# Switch.net
KiCad netlist of a schematic drawn in Altium Designer
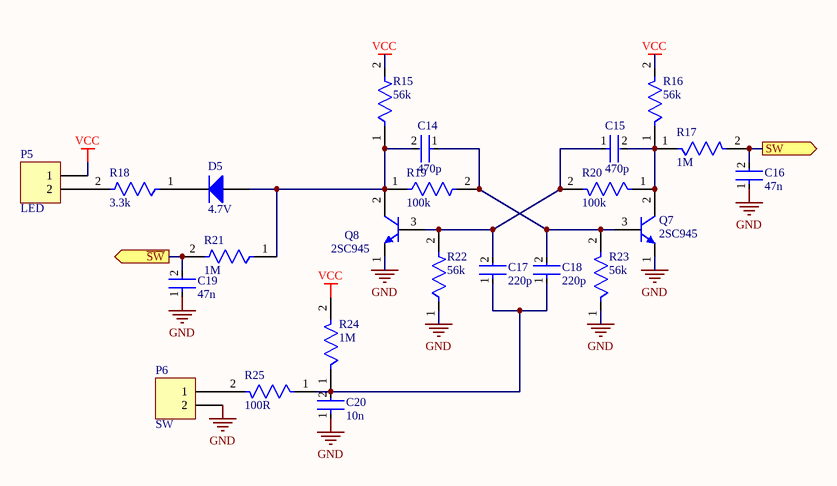
[diagram p0: Switch.SchDoc]

(export (version "E")
  (design (tool "Eeschema 10.0.6"))
  (components
    (comp (ref "C14")
      (value "470p")
      (footprint "FP-CL10-IPC_A")
      (description "Cap Ceramic 1nF 50V C0G ±5% Pad SMD 0603 +125°C T/R")
      (fields (field (name "VOLTAGE") "50V") (field (name "TOLERANCE") "5%"))
      (libsource (lib "Altium Content Vault") (part "b4654b650e69147ec39a6b967a45e02"))
    )
    (comp (ref "C15")
      (value "470p")
      (footprint "FP-CL10-IPC_A")
      (description "Cap Ceramic 1nF 50V C0G ±5% Pad SMD 0603 +125°C T/R")
      (fields (field (name "VOLTAGE") "50V") (field (name "TOLERANCE") "5%"))
      (libsource (lib "Altium Content Vault") (part "b4654b650e69147ec39a6b967a45e02"))
    )
    (comp (ref "C16")
      (value "47n")
      (footprint "FP-CL10-IPC_A")
      (description "Cap Ceramic 1nF 50V C0G ±5% Pad SMD 0603 +125°C T/R")
      (fields (field (name "VOLTAGE") "50V") (field (name "TOLERANCE") "5%"))
      (libsource (lib "Altium Content Vault") (part "b4654b650e69147ec39a6b967a45e02"))
    )
    (comp (ref "C17")
      (value "220p")
      (footprint "FP-CL10-IPC_A")
      (description "Cap Ceramic 1nF 50V C0G ±5% Pad SMD 0603 +125°C T/R")
      (fields (field (name "VOLTAGE") "50V") (field (name "TOLERANCE") "5%"))
      (libsource (lib "Altium Content Vault") (part "b4654b650e69147ec39a6b967a45e02"))
    )
    (comp (ref "C18")
      (value "220p")
      (footprint "FP-CL10-IPC_A")
      (description "Cap Ceramic 1nF 50V C0G ±5% Pad SMD 0603 +125°C T/R")
      (fields (field (name "VOLTAGE") "50V") (field (name "TOLERANCE") "5%"))
      (libsource (lib "Altium Content Vault") (part "b4654b650e69147ec39a6b967a45e02"))
    )
    (comp (ref "C19")
      (value "47n")
      (footprint "FP-CL10-IPC_A")
      (description "Cap Ceramic 1nF 50V C0G ±5% Pad SMD 0603 +125°C T/R")
      (fields (field (name "VOLTAGE") "50V") (field (name "TOLERANCE") "5%"))
      (libsource (lib "Altium Content Vault") (part "b4654b650e69147ec39a6b967a45e02"))
    )
    (comp (ref "C20")
      (value "10n")
      (footprint "FP-CL10-IPC_A")
      (description "Cap Ceramic 1nF 50V C0G ±5% Pad SMD 0603 +125°C T/R")
      (fields (field (name "VOLTAGE") "50V") (field (name "TOLERANCE") "5%"))
      (libsource (lib "Altium Content Vault") (part "b4654b650e69147ec39a6b967a45e02"))
    )
    (comp (ref "D5") (value "4.7V") (footprint "DO-41") (libsource (lib "TH_Symbols") (part "DIODE_SW")))
    (comp (ref "P5")
      (value "LED")
      (footprint "HDR1X2")
      (description "Header, 2-Pin")
      (fields (field (name "PUBLISHER") "Altium Limited"))
      (libsource (lib "Miscellaneous Connectors") (part "Header 2"))
    )
    (comp (ref "P6")
      (value "SW")
      (footprint "HDR1X2")
      (description "Header, 2-Pin")
      (fields (field (name "PUBLISHER") "Altium Limited"))
      (libsource (lib "Miscellaneous Connectors") (part "Header 2"))
    )
    (comp (ref "Q7") (value "2SC945") (footprint "TO-92") (libsource (lib "TH_Symbols") (part "BJT_NPN")))
    (comp (ref "Q8") (value "2SC945") (footprint "TO-92") (libsource (lib "TH_Symbols") (part "BJT_NPN")))
    (comp (ref "R15")
      (value "56k")
      (footprint "FP-RT0805-MFG")
      (description "RES SMD 10K OHM 0.1% 1/8W 0805")
      (fields
        (field (name "MANUFACTURER PART NUMBER") "RT0805BRE0710KL")
        (field (name "MANUFACTURER") "Yageo")
      )
      (libsource (lib "Altium Content Vault") (part "1029c3af85768c4190bb7ad29bc67b5"))
    )
    (comp (ref "R16")
      (value "56k")
      (footprint "FP-RT0805-MFG")
      (description "RES SMD 10K OHM 0.1% 1/8W 0805")
      (fields
        (field (name "MANUFACTURER PART NUMBER") "RT0805BRE0710KL")
        (field (name "MANUFACTURER") "Yageo")
      )
      (libsource (lib "Altium Content Vault") (part "1029c3af85768c4190bb7ad29bc67b5"))
    )
    (comp (ref "R17")
      (value "1M")
      (footprint "FP-RT0805-MFG")
      (description "RES SMD 10K OHM 0.1% 1/8W 0805")
      (fields
        (field (name "MANUFACTURER PART NUMBER") "RT0805BRE0710KL")
        (field (name "MANUFACTURER") "Yageo")
      )
      (libsource (lib "Altium Content Vault") (part "1029c3af85768c4190bb7ad29bc67b5"))
    )
    (comp (ref "R18")
      (value "3.3k")
      (footprint "FP-RT0805-MFG")
      (description "RES SMD 10K OHM 0.1% 1/8W 0805")
      (fields
        (field (name "MANUFACTURER PART NUMBER") "RT0805BRE0710KL")
        (field (name "MANUFACTURER") "Yageo")
      )
      (libsource (lib "Altium Content Vault") (part "1029c3af85768c4190bb7ad29bc67b5"))
    )
    (comp (ref "R19")
      (value "100k")
      (footprint "FP-RT0805-MFG")
      (description "RES SMD 10K OHM 0.1% 1/8W 0805")
      (fields
        (field (name "MANUFACTURER PART NUMBER") "RT0805BRE0710KL")
        (field (name "MANUFACTURER") "Yageo")
      )
      (libsource (lib "Altium Content Vault") (part "1029c3af85768c4190bb7ad29bc67b5"))
    )
    (comp (ref "R20")
      (value "100k")
      (footprint "FP-RT0805-MFG")
      (description "RES SMD 10K OHM 0.1% 1/8W 0805")
      (fields
        (field (name "MANUFACTURER PART NUMBER") "RT0805BRE0710KL")
        (field (name "MANUFACTURER") "Yageo")
      )
      (libsource (lib "Altium Content Vault") (part "1029c3af85768c4190bb7ad29bc67b5"))
    )
    (comp (ref "R21")
      (value "1M")
      (footprint "FP-RT0805-MFG")
      (description "RES SMD 10K OHM 0.1% 1/8W 0805")
      (fields
        (field (name "MANUFACTURER PART NUMBER") "RT0805BRE0710KL")
        (field (name "MANUFACTURER") "Yageo")
      )
      (libsource (lib "Altium Content Vault") (part "1029c3af85768c4190bb7ad29bc67b5"))
    )
    (comp (ref "R22")
      (value "56k")
      (footprint "FP-RT0805-MFG")
      (description "RES SMD 10K OHM 0.1% 1/8W 0805")
      (fields
        (field (name "MANUFACTURER PART NUMBER") "RT0805BRE0710KL")
        (field (name "MANUFACTURER") "Yageo")
      )
      (libsource (lib "Altium Content Vault") (part "1029c3af85768c4190bb7ad29bc67b5"))
    )
    (comp (ref "R23")
      (value "56k")
      (footprint "FP-RT0805-MFG")
      (description "RES SMD 10K OHM 0.1% 1/8W 0805")
      (fields
        (field (name "MANUFACTURER PART NUMBER") "RT0805BRE0710KL")
        (field (name "MANUFACTURER") "Yageo")
      )
      (libsource (lib "Altium Content Vault") (part "1029c3af85768c4190bb7ad29bc67b5"))
    )
    (comp (ref "R24")
      (value "1M")
      (footprint "FP-RT0805-MFG")
      (description "RES SMD 10K OHM 0.1% 1/8W 0805")
      (fields
        (field (name "MANUFACTURER PART NUMBER") "RT0805BRE0710KL")
        (field (name "MANUFACTURER") "Yageo")
      )
      (libsource (lib "Altium Content Vault") (part "1029c3af85768c4190bb7ad29bc67b5"))
    )
    (comp (ref "R25")
      (value "100R")
      (footprint "FP-RT0805-MFG")
      (description "RES SMD 10K OHM 0.1% 1/8W 0805")
      (fields
        (field (name "MANUFACTURER PART NUMBER") "RT0805BRE0710KL")
        (field (name "MANUFACTURER") "Yageo")
      )
      (libsource (lib "Altium Content Vault") (part "1029c3af85768c4190bb7ad29bc67b5"))
    )
  )
  (nets
    (net (code "1") (name "/SW") (class "Default")
      (node (ref "C16") (pin "2") (pinfunction "2_2") (pintype "passive"))
      (node (ref "R17") (pin "2") (pinfunction "2_2") (pintype "passive"))
    )
    (net (code "2") (name "/~{SW}") (class "Default")
      (node (ref "C19") (pin "2") (pinfunction "2_2") (pintype "passive"))
      (node (ref "R21") (pin "2") (pinfunction "2_2") (pintype "passive"))
    )
    (net (code "3") (name "GND") (class "Default")
      (node (ref "C16") (pin "1") (pinfunction "1_1") (pintype "passive"))
      (node (ref "C19") (pin "1") (pinfunction "1_1") (pintype "passive"))
      (node (ref "C20") (pin "1") (pinfunction "1_1") (pintype "passive"))
      (node (ref "P6") (pin "2") (pinfunction "2_2") (pintype "passive"))
      (node (ref "Q7") (pin "1") (pinfunction "E_1") (pintype "passive"))
      (node (ref "Q8") (pin "1") (pinfunction "E_1") (pintype "passive"))
      (node (ref "R22") (pin "1") (pinfunction "1_1") (pintype "passive"))
      (node (ref "R23") (pin "1") (pinfunction "1_1") (pintype "passive"))
    )
    (net (code "4") (name "Net-(C17-Pad1)") (class "Default")
      (node (ref "C17") (pin "1") (pinfunction "1_1") (pintype "passive"))
      (node (ref "C18") (pin "1") (pinfunction "1_1") (pintype "passive"))
      (node (ref "C20") (pin "2") (pinfunction "2_2") (pintype "passive"))
      (node (ref "R24") (pin "1") (pinfunction "1_1") (pintype "passive"))
      (node (ref "R25") (pin "1") (pinfunction "1_1") (pintype "passive"))
    )
    (net (code "5") (name "Net-(D5-A)") (class "Default")
      (node (ref "C14") (pin "2") (pinfunction "2_2") (pintype "passive"))
      (node (ref "D5") (pin "1") (pinfunction "A_1") (pintype "passive"))
      (node (ref "Q8") (pin "2") (pinfunction "C_2") (pintype "passive"))
      (node (ref "R15") (pin "1") (pinfunction "1_1") (pintype "passive"))
      (node (ref "R19") (pin "1") (pinfunction "1_1") (pintype "passive"))
      (node (ref "R21") (pin "1") (pinfunction "1_1") (pintype "passive"))
    )
    (net (code "6") (name "Net-(D5-K)") (class "Default")
      (node (ref "D5") (pin "2") (pinfunction "K_2") (pintype "passive"))
      (node (ref "R18") (pin "1") (pinfunction "1_1") (pintype "passive"))
    )
    (net (code "7") (name "Net-(P5-Pad2)") (class "Default")
      (node (ref "P5") (pin "2") (pinfunction "2_2") (pintype "passive"))
      (node (ref "R18") (pin "2") (pinfunction "2_2") (pintype "passive"))
    )
    (net (code "8") (name "Net-(P6-Pad1)") (class "Default")
      (node (ref "P6") (pin "1") (pinfunction "1_1") (pintype "passive"))
      (node (ref "R25") (pin "2") (pinfunction "2_2") (pintype "passive"))
    )
    (net (code "9") (name "Net-(Q7-B)") (class "Default")
      (node (ref "C14") (pin "1") (pinfunction "1_1") (pintype "passive"))
      (node (ref "C18") (pin "2") (pinfunction "2_2") (pintype "passive"))
      (node (ref "Q7") (pin "3") (pinfunction "B_3") (pintype "passive"))
      (node (ref "R19") (pin "2") (pinfunction "2_2") (pintype "passive"))
      (node (ref "R23") (pin "2") (pinfunction "2_2") (pintype "passive"))
    )
    (net (code "10") (name "Net-(Q7-C)") (class "Default")
      (node (ref "C15") (pin "2") (pinfunction "2_2") (pintype "passive"))
      (node (ref "Q7") (pin "2") (pinfunction "C_2") (pintype "passive"))
      (node (ref "R16") (pin "1") (pinfunction "1_1") (pintype "passive"))
      (node (ref "R17") (pin "1") (pinfunction "1_1") (pintype "passive"))
      (node (ref "R20") (pin "1") (pinfunction "1_1") (pintype "passive"))
    )
    (net (code "11") (name "Net-(Q8-B)") (class "Default")
      (node (ref "C15") (pin "1") (pinfunction "1_1") (pintype "passive"))
      (node (ref "C17") (pin "2") (pinfunction "2_2") (pintype "passive"))
      (node (ref "Q8") (pin "3") (pinfunction "B_3") (pintype "passive"))
      (node (ref "R20") (pin "2") (pinfunction "2_2") (pintype "passive"))
      (node (ref "R22") (pin "2") (pinfunction "2_2") (pintype "passive"))
    )
    (net (code "12") (name "VCC") (class "Default")
      (node (ref "P5") (pin "1") (pinfunction "1_1") (pintype "passive"))
      (node (ref "R15") (pin "2") (pinfunction "2_2") (pintype "passive"))
      (node (ref "R16") (pin "2") (pinfunction "2_2") (pintype "passive"))
      (node (ref "R24") (pin "2") (pinfunction "2_2") (pintype "passive"))
    )
  )
)
